# DanielRossi1_EdgePowerMeter__Manufacture.net
KiCad netlist of a schematic drawn in Altium Designer
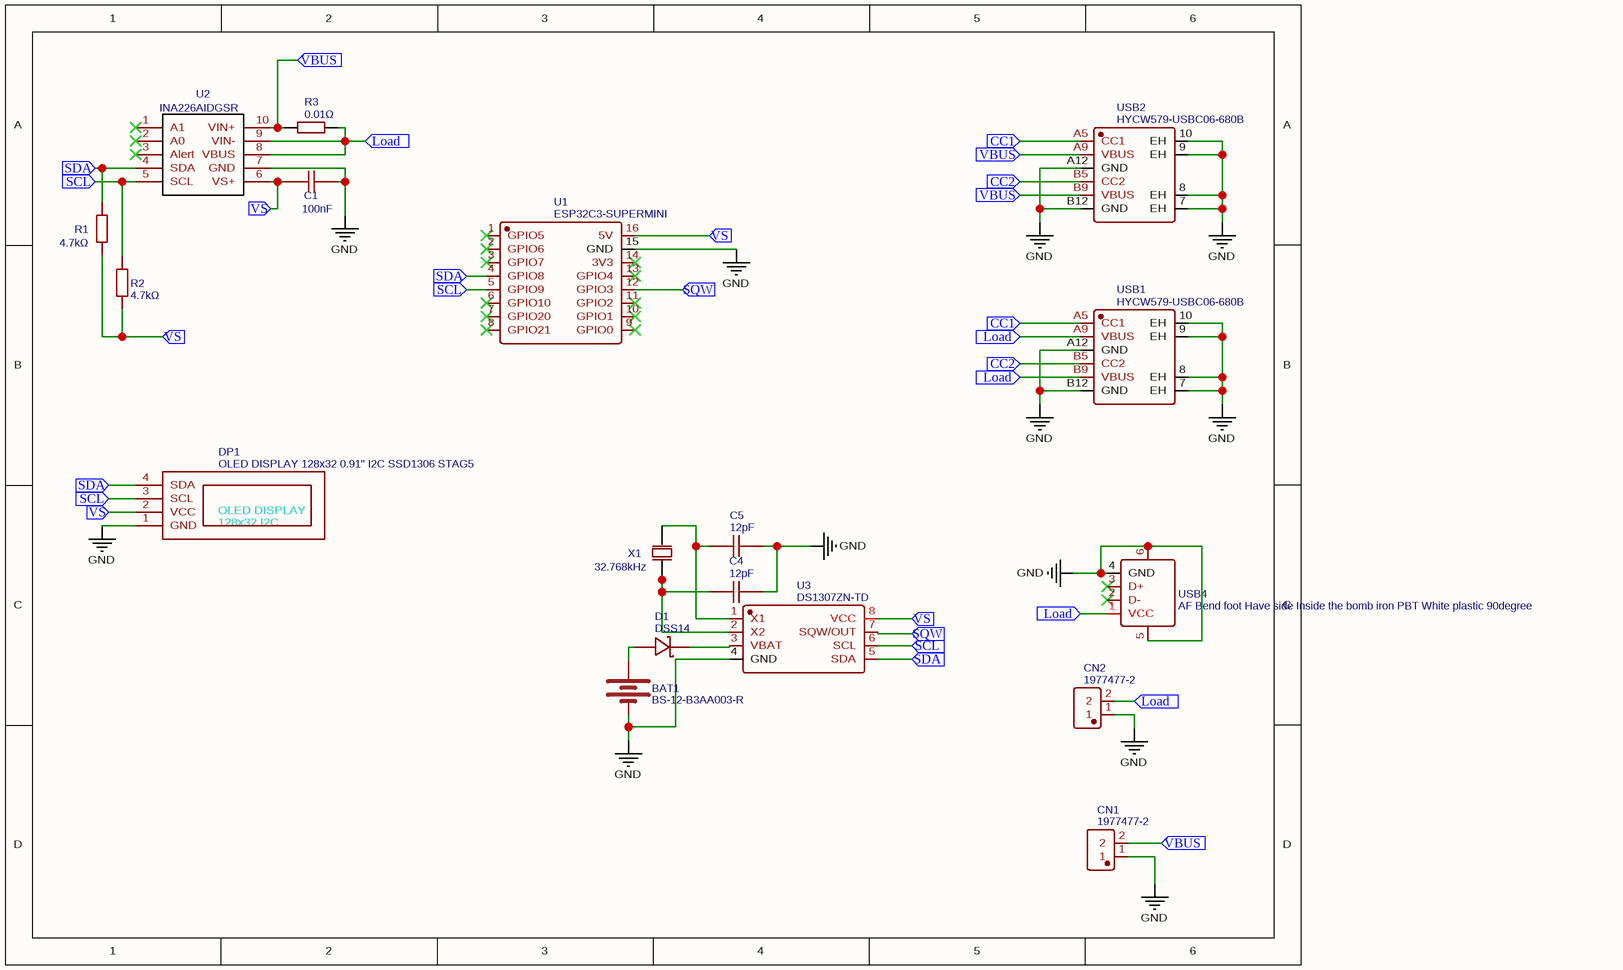
[diagram p0: DanielRossi1_EdgePowerMeter__Manufacture__EdgePowerMeter_Altium.schdoc]

(export (version "E")
  (design (tool "Eeschema 10.0.6"))
  (components
    (comp (ref "BAT1")
      (value "BS-12-B3AA003-R")
      (fields (field (name "MANUFACTURER") "MYOUNG(美阳)") (field (name "CONTRIBUTOR") "lcsc"))
      (libsource (lib "altium-import") (part "root_3_BS-12-B3AA003-R_"))
    )
    (comp (ref "C1")
      (value "100nF")
      (fields
        (field (name "MANUFACTURER") "KEMET(基美)")
        (field (name "MANUFACTURER PART") "C1206F104K1RAC3083")
        (field (name "CONTRIBUTOR") "LCSC")
      )
      (libsource (lib "altium-import") (part "root_1_100nF_"))
    )
    (comp (ref "C4")
      (value "12pF")
      (fields (field (name "CONTRIBUTOR") "LCSC"))
      (libsource (lib "altium-import") (part "root_2_12pF_"))
    )
    (comp (ref "C5")
      (value "12pF")
      (fields (field (name "CONTRIBUTOR") "LCSC"))
      (libsource (lib "altium-import") (part "root_0_12pF_"))
    )
    (comp (ref "CN1")
      (value "1977477-2")
      (fields (field (name "MANUFACTURER") "TE Connectivity(泰科电子)") (field (name "CONTRIBUTOR") "lcsc"))
      (libsource (lib "altium-import") (part "root_2_1977477-2_"))
    )
    (comp (ref "CN2")
      (value "1977477-2")
      (fields (field (name "MANUFACTURER") "TE Connectivity(泰科电子)") (field (name "CONTRIBUTOR") "lcsc"))
      (libsource (lib "altium-import") (part "root_2_1977477-2_"))
    )
    (comp (ref "D1")
      (value "DSS14")
      (fields (field (name "MANUFACTURER") "星海"))
      (libsource (lib "altium-import") (part "root_2_DSS14_"))
    )
    (comp (ref "DP1")
      (value "OLED DISPLAY 128x32 0.91\" I2C SSD1306 STAG5")
      (fields (field (name "CONTRIBUTOR") "priyasai1501"))
      (libsource (lib "altium-import") (part "root_0_OLED DISPLAY 128x32 0.91{dblquote} I2C SSD1306 STAG5_"))
    )
    (comp (ref "R1")
      (value "4.7kΩ")
      (fields
        (field (name "MANUFACTURER") "Tyohm(幸亚电阻)")
        (field (name "MANUFACTURER PART") "RMC12064.7K1%N")
        (field (name "CONTRIBUTOR") "LCSC")
      )
      (libsource (lib "altium-import") (part "root_1_4.7kΩ_"))
    )
    (comp (ref "R2")
      (value "4.7kΩ")
      (fields
        (field (name "MANUFACTURER") "Tyohm(幸亚电阻)")
        (field (name "MANUFACTURER PART") "RMC12064.7K1%N")
        (field (name "CONTRIBUTOR") "LCSC")
      )
      (libsource (lib "altium-import") (part "root_1_4.7kΩ_"))
    )
    (comp (ref "R3")
      (value "0.01Ω")
      (fields (field (name "MANUFACTURER PART") "MRF6432(2512)LR010JTS") (field (name "MANUFACTURER") "SUP"))
      (libsource (lib "altium-import") (part "root_0_0.01Ω_"))
    )
    (comp (ref "U1")
      (value "ESP32C3-SUPERMINI")
      (fields (field (name "MANUFACTURER PART") "ESP32C3-SuperMini") (field (name "CONTRIBUTOR") "lcsc"))
      (libsource (lib "altium-import") (part "root_0_ESP32C3-SUPERMINI_"))
    )
    (comp (ref "U2")
      (value "INA226AIDGSR")
      (fields (field (name "MANUFACTURER") "TI(德州仪器)"))
      (libsource (lib "altium-import") (part "root_0_INA226AIDGSR_"))
    )
    (comp (ref "U3")
      (value "DS1307ZN-TD")
      (fields (field (name "MANUFACTURER") "TDSEMIC(拓电半导体)") (field (name "CONTRIBUTOR") "lcsc"))
      (libsource (lib "altium-import") (part "root_0_DS1307ZN-TD_"))
    )
    (comp (ref "USB1")
      (value "HYCW579-USBC06-680B")
      (fields (field (name "MANUFACTURER") "华宇创") (field (name "CONTRIBUTOR") "lcsc"))
      (libsource (lib "altium-import") (part "root_0_HYCW579-USBC06-680B_"))
    )
    (comp (ref "USB2")
      (value "HYCW579-USBC06-680B")
      (fields (field (name "MANUFACTURER") "华宇创") (field (name "CONTRIBUTOR") "lcsc"))
      (libsource (lib "altium-import") (part "root_0_HYCW579-USBC06-680B_"))
    )
    (comp (ref "USB4")
      (value "AF Bend foot Have side Inside the bomb iron PBT White plastic 90degree")
      (fields (field (name "MANUFACTURER") "精拓金") (field (name "MANUFACTURER PART") "901-131A1011D10100"))
      (libsource (lib "altium-import") (part "root_2_AF Bend foot Have side Inside the bomb iron PBT White plastic 90degree_"))
    )
    (comp (ref "X1")
      (value "32.768kHz")
      (fields
        (field (name "MANUFACTURER") "ABRACON")
        (field (name "MANUFACTURER PART") "ABS07-120-32.768KHZ-T")
        (field (name "CONTRIBUTOR") "LCSC")
      )
      (libsource (lib "altium-import") (part "root_1_32.768kHz_"))
    )
  )
  (nets
    (net (code "1") (name "/CC1") (class "Default")
      (node (ref "USB1") (pin "A5") (pinfunction "CC1_A5") (pintype "passive"))
      (node (ref "USB2") (pin "A5") (pinfunction "CC1_A5") (pintype "passive"))
    )
    (net (code "2") (name "/CC2") (class "Default")
      (node (ref "USB1") (pin "B5") (pinfunction "CC2_B5") (pintype "passive"))
      (node (ref "USB2") (pin "B5") (pinfunction "CC2_B5") (pintype "passive"))
    )
    (net (code "3") (name "/Load") (class "Default")
      (node (ref "CN2") (pin "2") (pinfunction "2_2") (pintype "passive"))
      (node (ref "R3") (pin "2") (pinfunction "2_2") (pintype "passive"))
      (node (ref "U2") (pin "8") (pinfunction "VBUS_8") (pintype "passive"))
      (node (ref "U2") (pin "9") (pinfunction "VIN-_9") (pintype "passive"))
      (node (ref "USB1") (pin "A9") (pinfunction "VBUS_A9") (pintype "passive"))
      (node (ref "USB1") (pin "B9") (pinfunction "VBUS_B9") (pintype "passive"))
      (node (ref "USB4") (pin "1") (pinfunction "VCC_1") (pintype "passive"))
    )
    (net (code "4") (name "/SCL") (class "Default")
      (node (ref "DP1") (pin "3") (pinfunction "SCL_3") (pintype "passive"))
      (node (ref "R2") (pin "2") (pinfunction "2_2") (pintype "passive"))
      (node (ref "U1") (pin "5") (pinfunction "GPIO9_5") (pintype "passive"))
      (node (ref "U2") (pin "5") (pinfunction "SCL_5") (pintype "passive"))
      (node (ref "U3") (pin "6") (pinfunction "SCL_6") (pintype "passive"))
    )
    (net (code "5") (name "/SDA") (class "Default")
      (node (ref "DP1") (pin "4") (pinfunction "SDA_4") (pintype "passive"))
      (node (ref "R1") (pin "2") (pinfunction "2_2") (pintype "passive"))
      (node (ref "U1") (pin "4") (pinfunction "GPIO8_4") (pintype "passive"))
      (node (ref "U2") (pin "4") (pinfunction "SDA_4") (pintype "passive"))
      (node (ref "U3") (pin "5") (pinfunction "SDA_5") (pintype "passive"))
    )
    (net (code "6") (name "/SQW") (class "Default")
      (node (ref "U1") (pin "12") (pinfunction "GPIO3_12") (pintype "passive"))
      (node (ref "U3") (pin "7") (pinfunction "SQW/OUT_7") (pintype "passive"))
    )
    (net (code "7") (name "/VBUS") (class "Default")
      (node (ref "CN1") (pin "2") (pinfunction "2_2") (pintype "passive"))
      (node (ref "R3") (pin "1") (pinfunction "1_1") (pintype "passive"))
      (node (ref "U2") (pin "10") (pinfunction "VIN+_10") (pintype "passive"))
      (node (ref "USB2") (pin "A9") (pinfunction "VBUS_A9") (pintype "passive"))
      (node (ref "USB2") (pin "B9") (pinfunction "VBUS_B9") (pintype "passive"))
    )
    (net (code "8") (name "/VS") (class "Default")
      (node (ref "C1") (pin "2") (pinfunction "2_2") (pintype "passive"))
      (node (ref "DP1") (pin "2") (pinfunction "VCC_2") (pintype "passive"))
      (node (ref "R1") (pin "1") (pinfunction "1_1") (pintype "passive"))
      (node (ref "R2") (pin "1") (pinfunction "1_1") (pintype "passive"))
      (node (ref "U1") (pin "16") (pinfunction "5V_16") (pintype "passive"))
      (node (ref "U2") (pin "6") (pinfunction "VS+_6") (pintype "passive"))
      (node (ref "U3") (pin "8") (pinfunction "VCC_8") (pintype "passive"))
    )
    (net (code "9") (name "GND") (class "Default")
      (node (ref "BAT1") (pin "2") (pinfunction "-_2") (pintype "passive"))
      (node (ref "C1") (pin "1") (pinfunction "1_1") (pintype "passive"))
      (node (ref "C4") (pin "1") (pinfunction "1_1") (pintype "passive"))
      (node (ref "C5") (pin "2") (pinfunction "2_2") (pintype "passive"))
      (node (ref "CN1") (pin "1") (pinfunction "1_1") (pintype "passive"))
      (node (ref "CN2") (pin "1") (pinfunction "1_1") (pintype "passive"))
      (node (ref "DP1") (pin "1") (pinfunction "GND_1") (pintype "passive"))
      (node (ref "U1") (pin "15") (pinfunction "GND_15") (pintype "passive"))
      (node (ref "U2") (pin "7") (pinfunction "GND_7") (pintype "passive"))
      (node (ref "U3") (pin "4") (pinfunction "GND_4") (pintype "passive"))
      (node (ref "USB1") (pin "10") (pinfunction "EH_10") (pintype "passive"))
      (node (ref "USB1") (pin "7") (pinfunction "EH_7") (pintype "passive"))
      (node (ref "USB1") (pin "8") (pinfunction "EH_8") (pintype "passive"))
      (node (ref "USB1") (pin "9") (pinfunction "EH_9") (pintype "passive"))
      (node (ref "USB1") (pin "A12") (pinfunction "GND_A12") (pintype "passive"))
      (node (ref "USB1") (pin "B12") (pinfunction "GND_B12") (pintype "passive"))
      (node (ref "USB2") (pin "10") (pinfunction "EH_10") (pintype "passive"))
      (node (ref "USB2") (pin "7") (pinfunction "EH_7") (pintype "passive"))
      (node (ref "USB2") (pin "8") (pinfunction "EH_8") (pintype "passive"))
      (node (ref "USB2") (pin "9") (pinfunction "EH_9") (pintype "passive"))
      (node (ref "USB2") (pin "A12") (pinfunction "GND_A12") (pintype "passive"))
      (node (ref "USB2") (pin "B12") (pinfunction "GND_B12") (pintype "passive"))
      (node (ref "USB4") (pin "4") (pinfunction "GND_4") (pintype "passive"))
      (node (ref "USB4") (pin "5") (pinfunction "SH2_5") (pintype "passive"))
      (node (ref "USB4") (pin "6") (pinfunction "SH1_6") (pintype "passive"))
    )
    (net (code "10") (name "Net-(BAT1-+)") (class "Default")
      (node (ref "BAT1") (pin "1") (pinfunction "+_1") (pintype "passive"))
      (node (ref "D1") (pin "2") (pinfunction "A_2") (pintype "passive"))
    )
    (net (code "11") (name "Net-(D1-K)") (class "Default")
      (node (ref "D1") (pin "1") (pinfunction "K_1") (pintype "passive"))
      (node (ref "U3") (pin "3") (pinfunction "VBAT_3") (pintype "passive"))
    )
    (net (code "12") (name "Net-(U3-X1)") (class "Default")
      (node (ref "C5") (pin "1") (pinfunction "1_1") (pintype "passive"))
      (node (ref "U3") (pin "1") (pinfunction "X1_1") (pintype "passive"))
      (node (ref "X1") (pin "2") (pinfunction "OSC2_2") (pintype "passive"))
    )
    (net (code "13") (name "Net-(U3-X2)") (class "Default")
      (node (ref "C4") (pin "2") (pinfunction "2_2") (pintype "passive"))
      (node (ref "U3") (pin "2") (pinfunction "X2_2") (pintype "passive"))
      (node (ref "X1") (pin "1") (pinfunction "OSC1_1") (pintype "passive"))
    )
    (net (code "14") (name "unconnected-(U1-3V3-Pad14)") (class "Default")
      (node (ref "U1") (pin "14") (pinfunction "3V3_14") (pintype "passive+no_connect"))
    )
    (net (code "15") (name "unconnected-(U1-GPIO0-Pad9)") (class "Default")
      (node (ref "U1") (pin "9") (pinfunction "GPIO0_9") (pintype "passive+no_connect"))
    )
    (net (code "16") (name "unconnected-(U1-GPIO1-Pad10)") (class "Default")
      (node (ref "U1") (pin "10") (pinfunction "GPIO1_10") (pintype "passive+no_connect"))
    )
    (net (code "17") (name "unconnected-(U1-GPIO2-Pad11)") (class "Default")
      (node (ref "U1") (pin "11") (pinfunction "GPIO2_11") (pintype "passive+no_connect"))
    )
    (net (code "18") (name "unconnected-(U1-GPIO4-Pad13)") (class "Default")
      (node (ref "U1") (pin "13") (pinfunction "GPIO4_13") (pintype "passive+no_connect"))
    )
    (net (code "19") (name "unconnected-(U1-GPIO5-Pad1)") (class "Default")
      (node (ref "U1") (pin "1") (pinfunction "GPIO5_1") (pintype "passive+no_connect"))
    )
    (net (code "20") (name "unconnected-(U1-GPIO6-Pad2)") (class "Default")
      (node (ref "U1") (pin "2") (pinfunction "GPIO6_2") (pintype "passive+no_connect"))
    )
    (net (code "21") (name "unconnected-(U1-GPIO7-Pad3)") (class "Default")
      (node (ref "U1") (pin "3") (pinfunction "GPIO7_3") (pintype "passive+no_connect"))
    )
    (net (code "22") (name "unconnected-(U1-GPIO10-Pad6)") (class "Default")
      (node (ref "U1") (pin "6") (pinfunction "GPIO10_6") (pintype "passive+no_connect"))
    )
    (net (code "23") (name "unconnected-(U1-GPIO20-Pad7)") (class "Default")
      (node (ref "U1") (pin "7") (pinfunction "GPIO20_7") (pintype "passive+no_connect"))
    )
    (net (code "24") (name "unconnected-(U1-GPIO21-Pad8)") (class "Default")
      (node (ref "U1") (pin "8") (pinfunction "GPIO21_8") (pintype "passive+no_connect"))
    )
    (net (code "25") (name "unconnected-(U2-A0-Pad2)") (class "Default")
      (node (ref "U2") (pin "2") (pinfunction "A0_2") (pintype "passive+no_connect"))
    )
    (net (code "26") (name "unconnected-(U2-A1-Pad1)") (class "Default")
      (node (ref "U2") (pin "1") (pinfunction "A1_1") (pintype "passive+no_connect"))
    )
    (net (code "27") (name "unconnected-(U2-Alert-Pad3)") (class "Default")
      (node (ref "U2") (pin "3") (pinfunction "Alert_3") (pintype "passive+no_connect"))
    )
    (net (code "28") (name "unconnected-(USB4-D+-Pad3)") (class "Default")
      (node (ref "USB4") (pin "3") (pinfunction "D+_3") (pintype "passive+no_connect"))
    )
    (net (code "29") (name "unconnected-(USB4-D--Pad2)") (class "Default")
      (node (ref "USB4") (pin "2") (pinfunction "D-_2") (pintype "passive+no_connect"))
    )
  )
)
